# Pinduino-Nano-Sys11a-AR.net
KiCad netlist of a schematic drawn in EAGLE
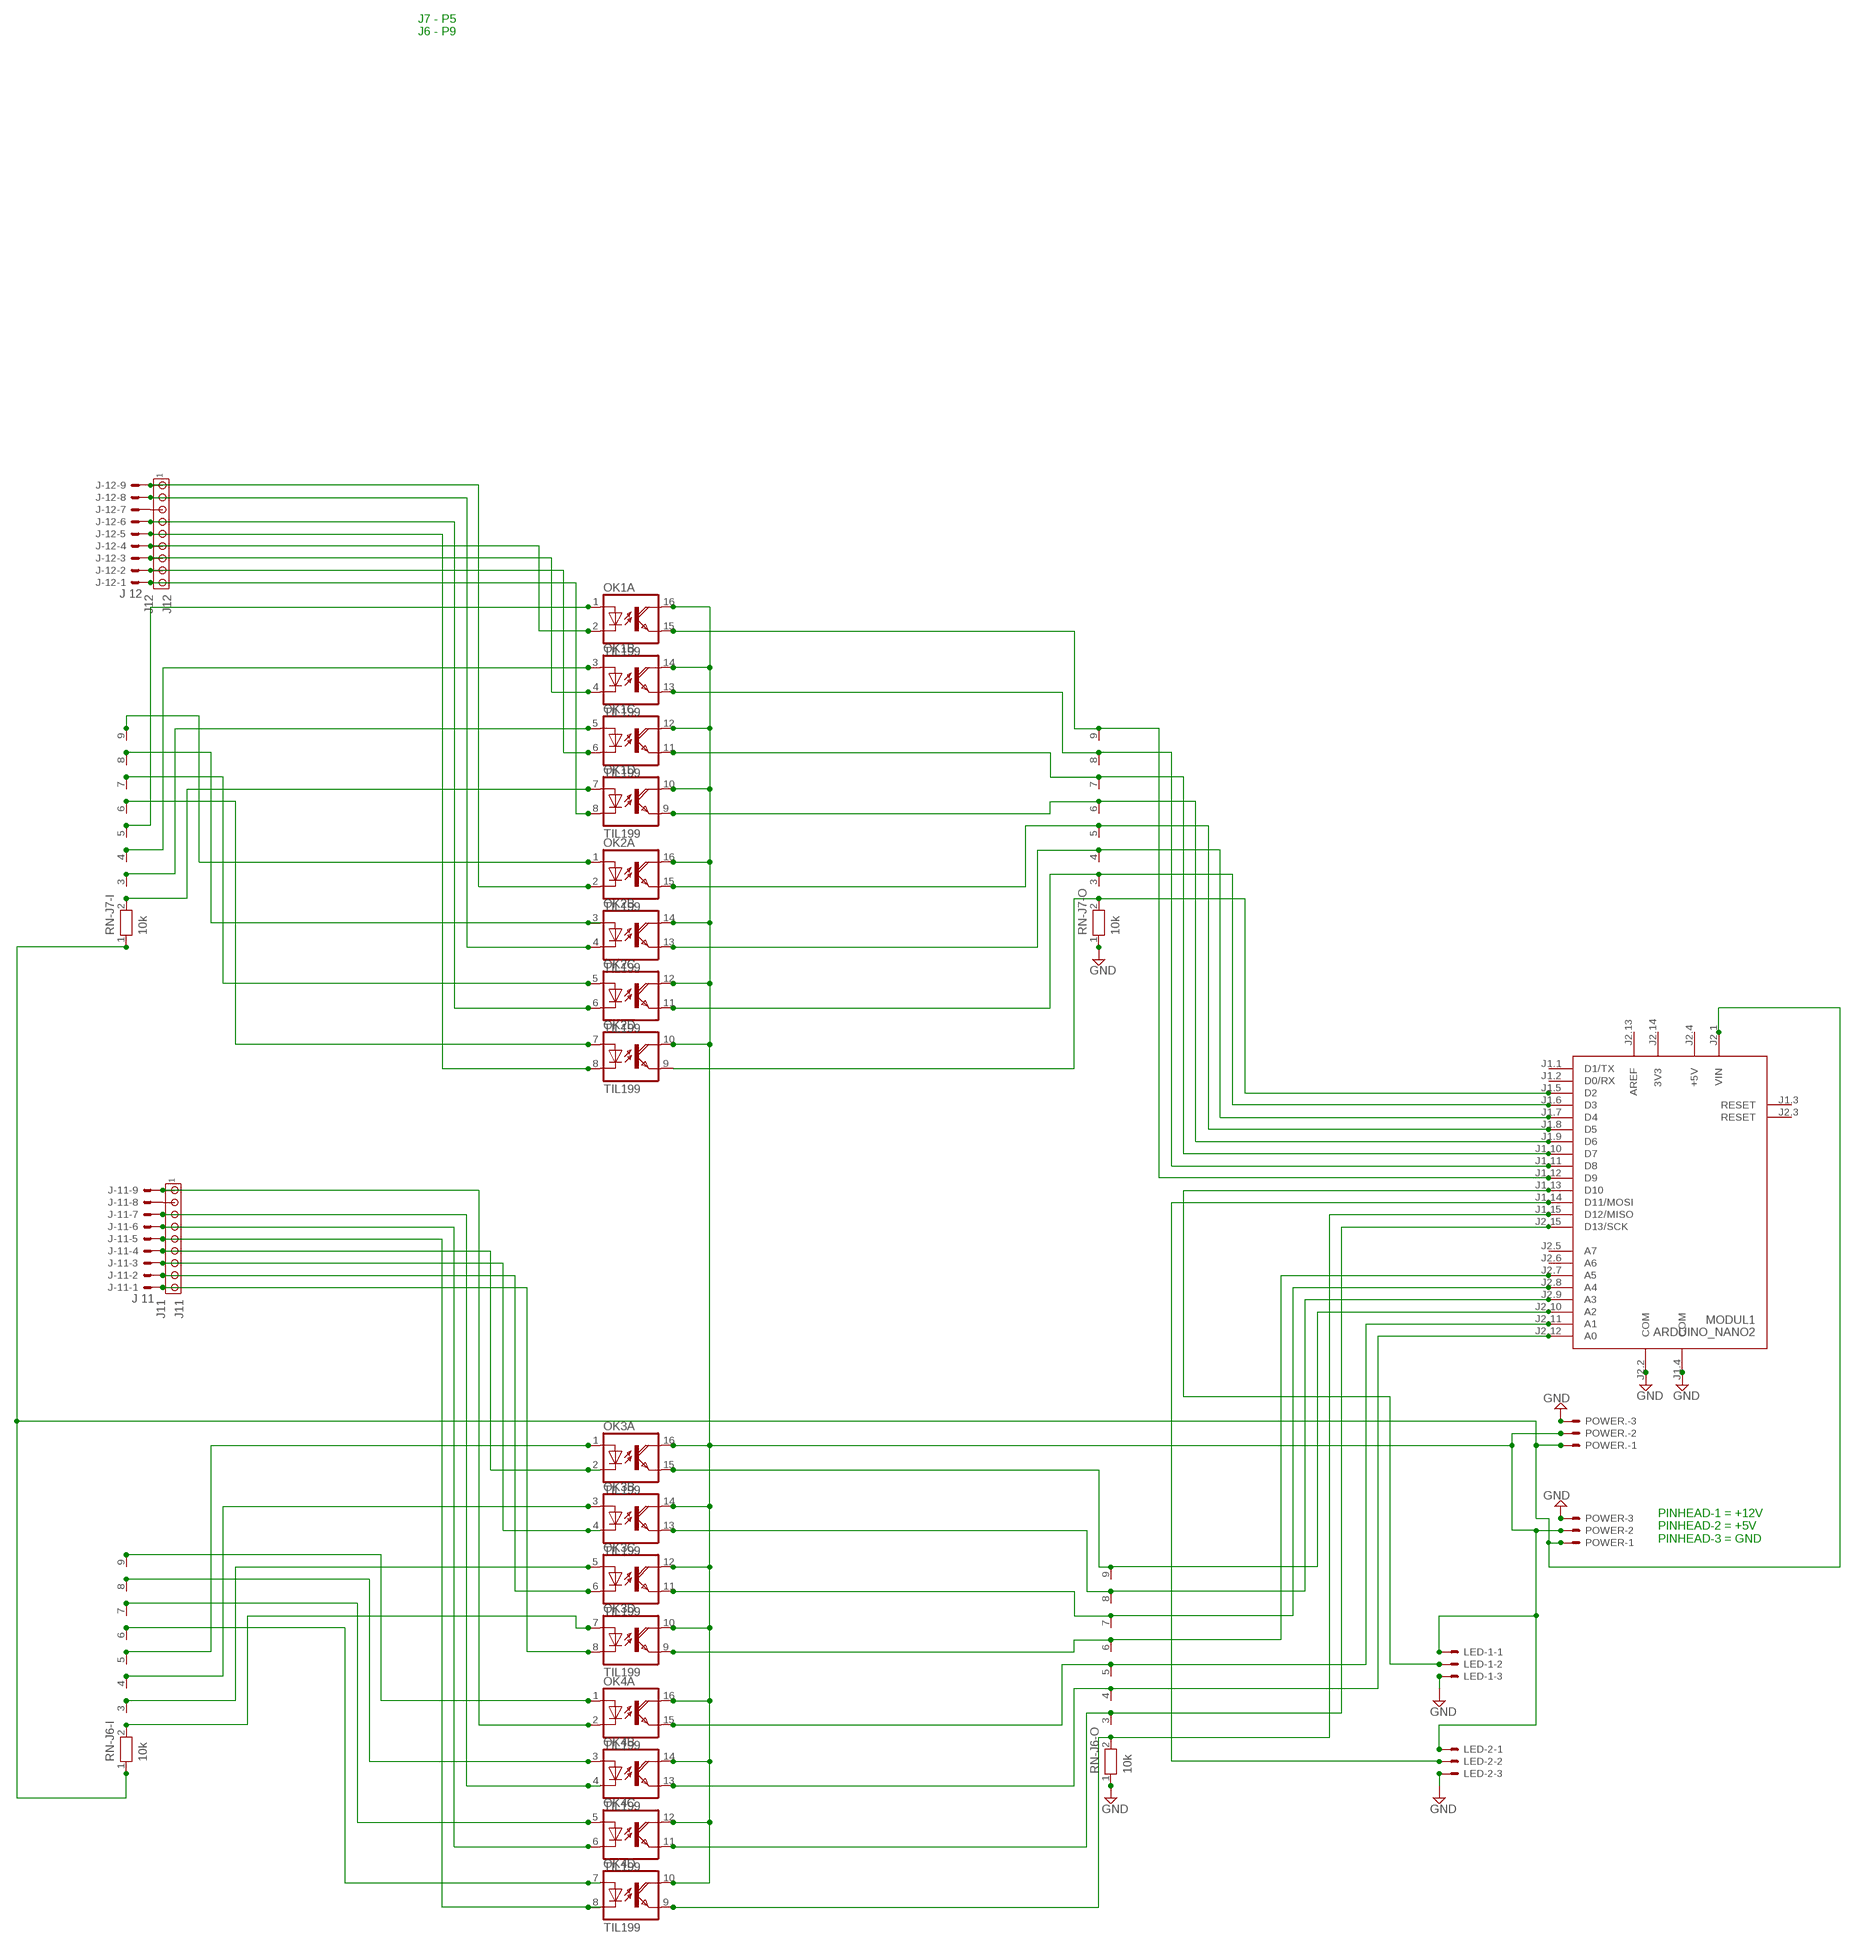
[diagram p0: schematic, sheet 1]

(export (version "E")
  (design (tool "Eeschema 10.0.6"))
  (components
    (comp (ref "J-11")
      (value "J 11")
      (footprint "eagle-import:KK-156-9")
      (libsource (lib "eagle-import") (part "KK-156-9"))
    )
    (comp (ref "J-12")
      (value "J 12")
      (footprint "eagle-import:KK-156-9")
      (libsource (lib "eagle-import") (part "KK-156-9"))
    )
    (comp (ref "J11")
      (value "J11")
      (footprint "eagle-import:1X9MTA")
      (libsource (lib "eagle-import") (part "MTA09-156"))
    )
    (comp (ref "J12")
      (value "J12")
      (footprint "eagle-import:1X9MTA")
      (libsource (lib "eagle-import") (part "MTA09-156"))
    )
    (comp (ref "LED-1")
      (value "22-23-2031")
      (footprint "eagle-import:22-23-2031")
      (fields (field (name "MF") "MOLEX"))
      (libsource (lib "eagle-import") (part "22-23-2031"))
    )
    (comp (ref "LED-2")
      (value "22-23-2031")
      (footprint "eagle-import:22-23-2031")
      (fields (field (name "MF") "MOLEX"))
      (libsource (lib "eagle-import") (part "22-23-2031"))
    )
    (comp (ref "MODUL1")
      (value "ARDUINO_NANO2")
      (footprint "eagle-import:ARDUINO_NANO2")
      (libsource (lib "eagle-import") (part "ARDUINO_NANO2"))
    )
    (comp (ref "OK1")
      (value "TIL199")
      (footprint "eagle-import:DIL16")
      (fields (field (name "MPN") "TIL 199"))
      (libsource (lib "eagle-import") (part "TIL199"))
    )
    (comp (ref "OK2")
      (value "TIL199")
      (footprint "eagle-import:DIL16")
      (fields (field (name "MPN") "TIL 199"))
      (libsource (lib "eagle-import") (part "TIL199"))
    )
    (comp (ref "OK3")
      (value "TIL199")
      (footprint "eagle-import:DIL16")
      (fields (field (name "MPN") "TIL 199"))
      (libsource (lib "eagle-import") (part "TIL199"))
    )
    (comp (ref "OK4")
      (value "TIL199")
      (footprint "eagle-import:DIL16")
      (fields (field (name "MPN") "TIL 199"))
      (libsource (lib "eagle-import") (part "TIL199"))
    )
    (comp (ref "POWER")
      (value "22-23-2031")
      (footprint "eagle-import:22-23-2031")
      (fields (field (name "MF") "MOLEX"))
      (libsource (lib "eagle-import") (part "22-23-2031"))
    )
    (comp (ref "POWER.")
      (value "22-23-2031")
      (footprint "eagle-import:22-23-2031")
      (fields (field (name "MF") "MOLEX"))
      (libsource (lib "eagle-import") (part "22-23-2031"))
    )
    (comp (ref "RN-J6-I")
      (value "10k")
      (footprint "eagle-import:RN-9")
      (libsource (lib "eagle-import") (part "RN08"))
    )
    (comp (ref "RN-J6-O")
      (value "10k")
      (footprint "eagle-import:RN-9")
      (libsource (lib "eagle-import") (part "RN08"))
    )
    (comp (ref "RN-J7-I")
      (value "10k")
      (footprint "eagle-import:RN-9")
      (libsource (lib "eagle-import") (part "RN08"))
    )
    (comp (ref "RN-J7-O")
      (value "10k")
      (footprint "eagle-import:RN-9")
      (libsource (lib "eagle-import") (part "RN08"))
    )
  )
  (nets
    (net (code "1") (name "/+5V") (class "Default")
      (node (ref "MODUL1") (pin "J2.4") (pinfunction "+5V_J2.4") (pintype "power_in"))
    )
    (net (code "2") (name "/3V3") (class "Default")
      (node (ref "MODUL1") (pin "J2.14") (pinfunction "3V3_J2.14") (pintype "power_in"))
    )
    (net (code "3") (name "/AREF") (class "Default")
      (node (ref "MODUL1") (pin "J2.13") (pinfunction "AREF_J2.13") (pintype "power_in"))
    )
    (net (code "4") (name "GND") (class "Default")
      (node (ref "LED-1") (pin "3") (pinfunction "S_3") (pintype "passive"))
      (node (ref "LED-2") (pin "3") (pinfunction "S_3") (pintype "passive"))
      (node (ref "MODUL1") (pin "J1.4") (pinfunction "COM_J1.4") (pintype "power_in"))
      (node (ref "MODUL1") (pin "J2.2") (pinfunction "COM_J2.2") (pintype "power_in"))
      (node (ref "POWER") (pin "3") (pinfunction "S_3") (pintype "passive"))
      (node (ref "POWER.") (pin "3") (pinfunction "S_3") (pintype "passive"))
      (node (ref "RN-J6-O") (pin "1") (pinfunction "1_1") (pintype "passive"))
      (node (ref "RN-J7-O") (pin "1") (pinfunction "1_1") (pintype "passive"))
    )
    (net (code "5") (name "Net-(J-11A-S)") (class "Default")
      (node (ref "J-11") (pin "1") (pinfunction "S_1") (pintype "passive"))
      (node (ref "J11") (pin "9") (pinfunction "9_9") (pintype "passive"))
      (node (ref "OK3") (pin "8") (pinfunction "C_8") (pintype "passive"))
    )
    (net (code "6") (name "Net-(J-11B-S)") (class "Default")
      (node (ref "J-11") (pin "2") (pinfunction "S_2") (pintype "passive"))
      (node (ref "J11") (pin "8") (pinfunction "8_8") (pintype "passive"))
      (node (ref "OK3") (pin "6") (pinfunction "C_6") (pintype "passive"))
    )
    (net (code "7") (name "Net-(J-11C-S)") (class "Default")
      (node (ref "J-11") (pin "3") (pinfunction "S_3") (pintype "passive"))
      (node (ref "J11") (pin "7") (pinfunction "7_7") (pintype "passive"))
      (node (ref "OK3") (pin "4") (pinfunction "C_4") (pintype "passive"))
    )
    (net (code "8") (name "Net-(J-11D-S)") (class "Default")
      (node (ref "J-11") (pin "4") (pinfunction "S_4") (pintype "passive"))
      (node (ref "J11") (pin "6") (pinfunction "6_6") (pintype "passive"))
      (node (ref "OK3") (pin "2") (pinfunction "C_2") (pintype "passive"))
    )
    (net (code "9") (name "Net-(J-11E-S)") (class "Default")
      (node (ref "J-11") (pin "5") (pinfunction "S_5") (pintype "passive"))
      (node (ref "J11") (pin "5") (pinfunction "5_5") (pintype "passive"))
      (node (ref "OK4") (pin "8") (pinfunction "C_8") (pintype "passive"))
    )
    (net (code "10") (name "Net-(J-11F-S)") (class "Default")
      (node (ref "J-11") (pin "6") (pinfunction "S_6") (pintype "passive"))
      (node (ref "J11") (pin "4") (pinfunction "4_4") (pintype "passive"))
      (node (ref "OK4") (pin "6") (pinfunction "C_6") (pintype "passive"))
    )
    (net (code "11") (name "Net-(J-11G-S)") (class "Default")
      (node (ref "J-11") (pin "7") (pinfunction "S_7") (pintype "passive"))
      (node (ref "J11") (pin "3") (pinfunction "3_3") (pintype "passive"))
      (node (ref "OK4") (pin "4") (pinfunction "C_4") (pintype "passive"))
    )
    (net (code "12") (name "Net-(J-11H-S)") (class "Default")
      (node (ref "J-11") (pin "8") (pinfunction "S_8") (pintype "passive"))
      (node (ref "J11") (pin "2") (pinfunction "2_2") (pintype "passive"))
    )
    (net (code "13") (name "Net-(J-11I-S)") (class "Default")
      (node (ref "J-11") (pin "9") (pinfunction "S_9") (pintype "passive"))
      (node (ref "J11") (pin "1") (pinfunction "1_1") (pintype "passive"))
      (node (ref "OK4") (pin "2") (pinfunction "C_2") (pintype "passive"))
    )
    (net (code "14") (name "Net-(J-12A-S)") (class "Default")
      (node (ref "J-12") (pin "1") (pinfunction "S_1") (pintype "passive"))
      (node (ref "J12") (pin "9") (pinfunction "9_9") (pintype "passive"))
      (node (ref "OK1") (pin "8") (pinfunction "C_8") (pintype "passive"))
    )
    (net (code "15") (name "Net-(J-12B-S)") (class "Default")
      (node (ref "J-12") (pin "2") (pinfunction "S_2") (pintype "passive"))
      (node (ref "J12") (pin "8") (pinfunction "8_8") (pintype "passive"))
      (node (ref "OK1") (pin "6") (pinfunction "C_6") (pintype "passive"))
    )
    (net (code "16") (name "Net-(J-12C-S)") (class "Default")
      (node (ref "J-12") (pin "3") (pinfunction "S_3") (pintype "passive"))
      (node (ref "J12") (pin "7") (pinfunction "7_7") (pintype "passive"))
      (node (ref "OK1") (pin "4") (pinfunction "C_4") (pintype "passive"))
    )
    (net (code "17") (name "Net-(J-12D-S)") (class "Default")
      (node (ref "J-12") (pin "4") (pinfunction "S_4") (pintype "passive"))
      (node (ref "J12") (pin "6") (pinfunction "6_6") (pintype "passive"))
      (node (ref "OK1") (pin "2") (pinfunction "C_2") (pintype "passive"))
    )
    (net (code "18") (name "Net-(J-12E-S)") (class "Default")
      (node (ref "J-12") (pin "5") (pinfunction "S_5") (pintype "passive"))
      (node (ref "J12") (pin "5") (pinfunction "5_5") (pintype "passive"))
      (node (ref "OK2") (pin "8") (pinfunction "C_8") (pintype "passive"))
    )
    (net (code "19") (name "Net-(J-12F-S)") (class "Default")
      (node (ref "J-12") (pin "6") (pinfunction "S_6") (pintype "passive"))
      (node (ref "J12") (pin "4") (pinfunction "4_4") (pintype "passive"))
      (node (ref "OK2") (pin "6") (pinfunction "C_6") (pintype "passive"))
    )
    (net (code "20") (name "Net-(J-12G-S)") (class "Default")
      (node (ref "J-12") (pin "7") (pinfunction "S_7") (pintype "passive"))
      (node (ref "J12") (pin "3") (pinfunction "3_3") (pintype "passive"))
    )
    (net (code "21") (name "Net-(J-12H-S)") (class "Default")
      (node (ref "J-12") (pin "8") (pinfunction "S_8") (pintype "passive"))
      (node (ref "J12") (pin "2") (pinfunction "2_2") (pintype "passive"))
      (node (ref "OK2") (pin "4") (pinfunction "C_4") (pintype "passive"))
    )
    (net (code "22") (name "Net-(J-12I-S)") (class "Default")
      (node (ref "J-12") (pin "9") (pinfunction "S_9") (pintype "passive"))
      (node (ref "J12") (pin "1") (pinfunction "1_1") (pintype "passive"))
      (node (ref "OK2") (pin "2") (pinfunction "C_2") (pintype "passive"))
    )
    (net (code "23") (name "Net-(LED-1A-S)") (class "Default")
      (node (ref "LED-1") (pin "1") (pinfunction "S_1") (pintype "passive"))
      (node (ref "LED-2") (pin "1") (pinfunction "S_1") (pintype "passive"))
      (node (ref "OK1") (pin "10") (pinfunction "COL_10") (pintype "passive"))
      (node (ref "OK1") (pin "12") (pinfunction "COL_12") (pintype "passive"))
      (node (ref "OK1") (pin "14") (pinfunction "COL_14") (pintype "passive"))
      (node (ref "OK1") (pin "16") (pinfunction "COL_16") (pintype "passive"))
      (node (ref "OK2") (pin "10") (pinfunction "COL_10") (pintype "passive"))
      (node (ref "OK2") (pin "12") (pinfunction "COL_12") (pintype "passive"))
      (node (ref "OK2") (pin "14") (pinfunction "COL_14") (pintype "passive"))
      (node (ref "OK2") (pin "16") (pinfunction "COL_16") (pintype "passive"))
      (node (ref "OK3") (pin "10") (pinfunction "COL_10") (pintype "passive"))
      (node (ref "OK3") (pin "12") (pinfunction "COL_12") (pintype "passive"))
      (node (ref "OK3") (pin "14") (pinfunction "COL_14") (pintype "passive"))
      (node (ref "OK3") (pin "16") (pinfunction "COL_16") (pintype "passive"))
      (node (ref "OK4") (pin "10") (pinfunction "COL_10") (pintype "passive"))
      (node (ref "OK4") (pin "12") (pinfunction "COL_12") (pintype "passive"))
      (node (ref "OK4") (pin "14") (pinfunction "COL_14") (pintype "passive"))
      (node (ref "OK4") (pin "16") (pinfunction "COL_16") (pintype "passive"))
      (node (ref "POWER") (pin "2") (pinfunction "S_2") (pintype "passive"))
      (node (ref "POWER.") (pin "2") (pinfunction "S_2") (pintype "passive"))
    )
    (net (code "24") (name "Net-(LED-1B-S)") (class "Default")
      (node (ref "LED-1") (pin "2") (pinfunction "S_2") (pintype "passive"))
      (node (ref "MODUL1") (pin "J1.13") (pinfunction "D10_J1.13") (pintype "bidirectional"))
    )
    (net (code "25") (name "Net-(LED-2B-S)") (class "Default")
      (node (ref "LED-2") (pin "2") (pinfunction "S_2") (pintype "passive"))
      (node (ref "MODUL1") (pin "J1.14") (pinfunction "D11/MOSI_J1.14") (pintype "bidirectional"))
    )
    (net (code "26") (name "Net-(MODUL1-A0)") (class "Default")
      (node (ref "MODUL1") (pin "J2.12") (pinfunction "A0_J2.12") (pintype "bidirectional"))
      (node (ref "OK4") (pin "13") (pinfunction "EMI_13") (pintype "passive"))
      (node (ref "RN-J6-O") (pin "4") (pinfunction "4_4") (pintype "passive"))
    )
    (net (code "27") (name "Net-(MODUL1-A1)") (class "Default")
      (node (ref "MODUL1") (pin "J2.11") (pinfunction "A1_J2.11") (pintype "bidirectional"))
      (node (ref "OK4") (pin "15") (pinfunction "EMI_15") (pintype "passive"))
      (node (ref "RN-J6-O") (pin "5") (pinfunction "5_5") (pintype "passive"))
    )
    (net (code "28") (name "Net-(MODUL1-A2)") (class "Default")
      (node (ref "MODUL1") (pin "J2.10") (pinfunction "A2_J2.10") (pintype "bidirectional"))
      (node (ref "OK3") (pin "15") (pinfunction "EMI_15") (pintype "passive"))
      (node (ref "RN-J6-O") (pin "9") (pinfunction "9_9") (pintype "passive"))
    )
    (net (code "29") (name "Net-(MODUL1-A3)") (class "Default")
      (node (ref "MODUL1") (pin "J2.9") (pinfunction "A3_J2.9") (pintype "bidirectional"))
      (node (ref "OK3") (pin "13") (pinfunction "EMI_13") (pintype "passive"))
      (node (ref "RN-J6-O") (pin "8") (pinfunction "8_8") (pintype "passive"))
    )
    (net (code "30") (name "Net-(MODUL1-A4)") (class "Default")
      (node (ref "MODUL1") (pin "J2.8") (pinfunction "A4_J2.8") (pintype "bidirectional"))
      (node (ref "OK3") (pin "11") (pinfunction "EMI_11") (pintype "passive"))
      (node (ref "RN-J6-O") (pin "7") (pinfunction "7_7") (pintype "passive"))
    )
    (net (code "31") (name "Net-(MODUL1-A5)") (class "Default")
      (node (ref "MODUL1") (pin "J2.7") (pinfunction "A5_J2.7") (pintype "bidirectional"))
      (node (ref "OK3") (pin "9") (pinfunction "EMI_9") (pintype "passive"))
      (node (ref "RN-J6-O") (pin "6") (pinfunction "6_6") (pintype "passive"))
    )
    (net (code "32") (name "Net-(MODUL1-D2)") (class "Default")
      (node (ref "MODUL1") (pin "J1.5") (pinfunction "D2_J1.5") (pintype "bidirectional"))
      (node (ref "OK2") (pin "9") (pinfunction "EMI_9") (pintype "passive"))
      (node (ref "RN-J7-O") (pin "2") (pinfunction "2_2") (pintype "passive"))
    )
    (net (code "33") (name "Net-(MODUL1-D3)") (class "Default")
      (node (ref "MODUL1") (pin "J1.6") (pinfunction "D3_J1.6") (pintype "bidirectional"))
      (node (ref "OK2") (pin "11") (pinfunction "EMI_11") (pintype "passive"))
      (node (ref "RN-J7-O") (pin "3") (pinfunction "3_3") (pintype "passive"))
    )
    (net (code "34") (name "Net-(MODUL1-D4)") (class "Default")
      (node (ref "MODUL1") (pin "J1.7") (pinfunction "D4_J1.7") (pintype "bidirectional"))
      (node (ref "OK2") (pin "13") (pinfunction "EMI_13") (pintype "passive"))
      (node (ref "RN-J7-O") (pin "4") (pinfunction "4_4") (pintype "passive"))
    )
    (net (code "35") (name "Net-(MODUL1-D5)") (class "Default")
      (node (ref "MODUL1") (pin "J1.8") (pinfunction "D5_J1.8") (pintype "bidirectional"))
      (node (ref "OK2") (pin "15") (pinfunction "EMI_15") (pintype "passive"))
      (node (ref "RN-J7-O") (pin "5") (pinfunction "5_5") (pintype "passive"))
    )
    (net (code "36") (name "Net-(MODUL1-D6)") (class "Default")
      (node (ref "MODUL1") (pin "J1.9") (pinfunction "D6_J1.9") (pintype "bidirectional"))
      (node (ref "OK1") (pin "9") (pinfunction "EMI_9") (pintype "passive"))
      (node (ref "RN-J7-O") (pin "6") (pinfunction "6_6") (pintype "passive"))
    )
    (net (code "37") (name "Net-(MODUL1-D7)") (class "Default")
      (node (ref "MODUL1") (pin "J1.10") (pinfunction "D7_J1.10") (pintype "bidirectional"))
      (node (ref "OK1") (pin "11") (pinfunction "EMI_11") (pintype "passive"))
      (node (ref "RN-J7-O") (pin "7") (pinfunction "7_7") (pintype "passive"))
    )
    (net (code "38") (name "Net-(MODUL1-D8)") (class "Default")
      (node (ref "MODUL1") (pin "J1.11") (pinfunction "D8_J1.11") (pintype "bidirectional"))
      (node (ref "OK1") (pin "13") (pinfunction "EMI_13") (pintype "passive"))
      (node (ref "RN-J7-O") (pin "8") (pinfunction "8_8") (pintype "passive"))
    )
    (net (code "39") (name "Net-(MODUL1-D9)") (class "Default")
      (node (ref "MODUL1") (pin "J1.12") (pinfunction "D9_J1.12") (pintype "bidirectional"))
      (node (ref "OK1") (pin "15") (pinfunction "EMI_15") (pintype "passive"))
      (node (ref "RN-J7-O") (pin "9") (pinfunction "9_9") (pintype "passive"))
    )
    (net (code "40") (name "Net-(MODUL1-D12{slash}MISO)") (class "Default")
      (node (ref "MODUL1") (pin "J1.15") (pinfunction "D12/MISO_J1.15") (pintype "bidirectional"))
      (node (ref "OK4") (pin "9") (pinfunction "EMI_9") (pintype "passive"))
      (node (ref "RN-J6-O") (pin "2") (pinfunction "2_2") (pintype "passive"))
    )
    (net (code "41") (name "Net-(MODUL1-D13{slash}SCK)") (class "Default")
      (node (ref "MODUL1") (pin "J2.15") (pinfunction "D13/SCK_J2.15") (pintype "bidirectional"))
      (node (ref "OK4") (pin "11") (pinfunction "EMI_11") (pintype "passive"))
      (node (ref "RN-J6-O") (pin "3") (pinfunction "3_3") (pintype "passive"))
    )
    (net (code "42") (name "Net-(MODUL1-VIN)") (class "Default")
      (node (ref "MODUL1") (pin "J2.1") (pinfunction "VIN_J2.1") (pintype "power_in"))
      (node (ref "POWER") (pin "1") (pinfunction "S_1") (pintype "passive"))
      (node (ref "POWER.") (pin "1") (pinfunction "S_1") (pintype "passive"))
      (node (ref "RN-J6-I") (pin "1") (pinfunction "1_1") (pintype "passive"))
      (node (ref "RN-J7-I") (pin "1") (pinfunction "1_1") (pintype "passive"))
    )
    (net (code "43") (name "Net-(OK1A-A)") (class "Default")
      (node (ref "OK1") (pin "1") (pinfunction "A_1") (pintype "passive"))
      (node (ref "RN-J7-I") (pin "5") (pinfunction "5_5") (pintype "passive"))
    )
    (net (code "44") (name "Net-(OK1B-A)") (class "Default")
      (node (ref "OK1") (pin "3") (pinfunction "A_3") (pintype "passive"))
      (node (ref "RN-J7-I") (pin "4") (pinfunction "4_4") (pintype "passive"))
    )
    (net (code "45") (name "Net-(OK1C-A)") (class "Default")
      (node (ref "OK1") (pin "5") (pinfunction "A_5") (pintype "passive"))
      (node (ref "RN-J7-I") (pin "3") (pinfunction "3_3") (pintype "passive"))
    )
    (net (code "46") (name "Net-(OK1D-A)") (class "Default")
      (node (ref "OK1") (pin "7") (pinfunction "A_7") (pintype "passive"))
      (node (ref "RN-J7-I") (pin "2") (pinfunction "2_2") (pintype "passive"))
    )
    (net (code "47") (name "Net-(OK2A-A)") (class "Default")
      (node (ref "OK2") (pin "1") (pinfunction "A_1") (pintype "passive"))
      (node (ref "RN-J7-I") (pin "9") (pinfunction "9_9") (pintype "passive"))
    )
    (net (code "48") (name "Net-(OK2B-A)") (class "Default")
      (node (ref "OK2") (pin "3") (pinfunction "A_3") (pintype "passive"))
      (node (ref "RN-J7-I") (pin "8") (pinfunction "8_8") (pintype "passive"))
    )
    (net (code "49") (name "Net-(OK2C-A)") (class "Default")
      (node (ref "OK2") (pin "5") (pinfunction "A_5") (pintype "passive"))
      (node (ref "RN-J7-I") (pin "7") (pinfunction "7_7") (pintype "passive"))
    )
    (net (code "50") (name "Net-(OK2D-A)") (class "Default")
      (node (ref "OK2") (pin "7") (pinfunction "A_7") (pintype "passive"))
      (node (ref "RN-J7-I") (pin "6") (pinfunction "6_6") (pintype "passive"))
    )
    (net (code "51") (name "Net-(OK3A-A)") (class "Default")
      (node (ref "OK3") (pin "1") (pinfunction "A_1") (pintype "passive"))
      (node (ref "RN-J6-I") (pin "5") (pinfunction "5_5") (pintype "passive"))
    )
    (net (code "52") (name "Net-(OK3B-A)") (class "Default")
      (node (ref "OK3") (pin "3") (pinfunction "A_3") (pintype "passive"))
      (node (ref "RN-J6-I") (pin "4") (pinfunction "4_4") (pintype "passive"))
    )
    (net (code "53") (name "Net-(OK3C-A)") (class "Default")
      (node (ref "OK3") (pin "5") (pinfunction "A_5") (pintype "passive"))
      (node (ref "RN-J6-I") (pin "3") (pinfunction "3_3") (pintype "passive"))
    )
    (net (code "54") (name "Net-(OK3D-A)") (class "Default")
      (node (ref "OK3") (pin "7") (pinfunction "A_7") (pintype "passive"))
      (node (ref "RN-J6-I") (pin "2") (pinfunction "2_2") (pintype "passive"))
    )
    (net (code "55") (name "Net-(OK4A-A)") (class "Default")
      (node (ref "OK4") (pin "1") (pinfunction "A_1") (pintype "passive"))
      (node (ref "RN-J6-I") (pin "9") (pinfunction "9_9") (pintype "passive"))
    )
    (net (code "56") (name "Net-(OK4B-A)") (class "Default")
      (node (ref "OK4") (pin "3") (pinfunction "A_3") (pintype "passive"))
      (node (ref "RN-J6-I") (pin "8") (pinfunction "8_8") (pintype "passive"))
    )
    (net (code "57") (name "Net-(OK4C-A)") (class "Default")
      (node (ref "OK4") (pin "5") (pinfunction "A_5") (pintype "passive"))
      (node (ref "RN-J6-I") (pin "7") (pinfunction "7_7") (pintype "passive"))
    )
    (net (code "58") (name "Net-(OK4D-A)") (class "Default")
      (node (ref "OK4") (pin "7") (pinfunction "A_7") (pintype "passive"))
      (node (ref "RN-J6-I") (pin "6") (pinfunction "6_6") (pintype "passive"))
    )
    (net (code "59") (name "unconnected-(MODUL1-A6-PadJ2.6)") (class "Default")
      (node (ref "MODUL1") (pin "J2.6") (pinfunction "A6_J2.6") (pintype "bidirectional"))
    )
    (net (code "60") (name "unconnected-(MODUL1-A7-PadJ2.5)") (class "Default")
      (node (ref "MODUL1") (pin "J2.5") (pinfunction "A7_J2.5") (pintype "bidirectional"))
    )
    (net (code "61") (name "unconnected-(MODUL1-D0{slash}RX-PadJ1.2)") (class "Default")
      (node (ref "MODUL1") (pin "J1.2") (pinfunction "D0/RX_J1.2") (pintype "bidirectional"))
    )
    (net (code "62") (name "unconnected-(MODUL1-D1{slash}TX-PadJ1.1)") (class "Default")
      (node (ref "MODUL1") (pin "J1.1") (pinfunction "D1/TX_J1.1") (pintype "bidirectional"))
    )
    (net (code "63") (name "unconnected-(MODUL1-RESET-PadJ1.3)") (class "Default")
      (node (ref "MODUL1") (pin "J1.3") (pinfunction "RESET_J1.3") (pintype "bidirectional"))
    )
    (net (code "64") (name "unconnected-(MODUL1-RESET-PadJ2.3)") (class "Default")
      (node (ref "MODUL1") (pin "J2.3") (pinfunction "RESET_J2.3") (pintype "bidirectional"))
    )
  )
)
